# JTAG_Connector.net
KiCad netlist of a schematic drawn in Altium Designer
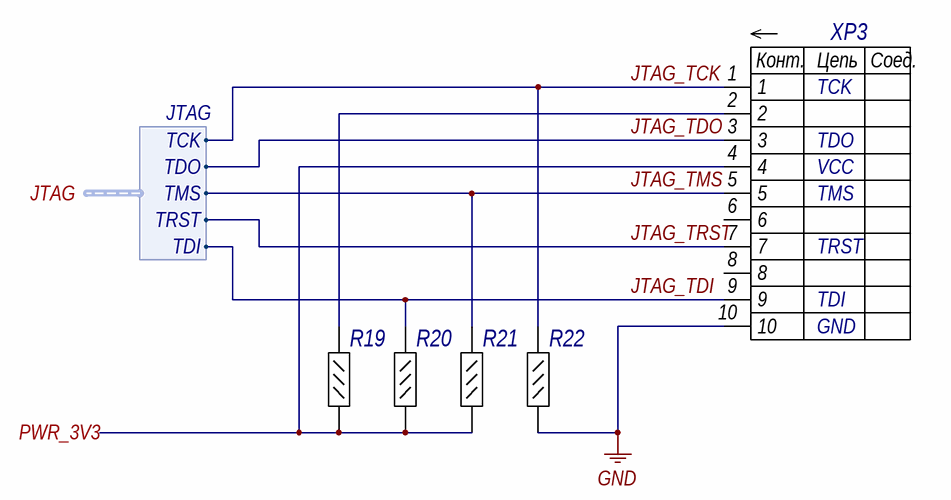
[diagram p0: JTAG Connector.SchDoc]

(export (version "E")
  (design (tool "Eeschema 10.0.6"))
  (components
    (comp (ref "R19")
      (value "ERJ-2RKF1001X")
      (footprint "RESC1005X40X25LL05T05")
      (description "Chip Resistor, 1 KOhm, +/- 1%, 100 mW, -55 to 155 degC, 0402 (1005 Metric), RoHS, Tape and Reel")
      (fields (field (name "TOLERANCE") "1%") (field (name "MANUFACTURER") "Basic Passives"))
      (libsource (lib "") (part "RES-0.05_1"))
    )
    (comp (ref "R20")
      (value "ERJ-2RKF1001X")
      (footprint "RESC1005X40X25LL05T05")
      (description "Chip Resistor, 1 KOhm, +/- 1%, 100 mW, -55 to 155 degC, 0402 (1005 Metric), RoHS, Tape and Reel")
      (fields (field (name "TOLERANCE") "1%") (field (name "MANUFACTURER") "Basic Passives"))
      (libsource (lib "MiniPC DB") (part "RES-0.05"))
    )
    (comp (ref "R21")
      (value "ERJ-2RKF1001X")
      (footprint "RESC1005X40X25LL05T05")
      (description "Chip Resistor, 1 KOhm, +/- 1%, 100 mW, -55 to 155 degC, 0402 (1005 Metric), RoHS, Tape and Reel")
      (fields (field (name "TOLERANCE") "1%") (field (name "MANUFACTURER") "Basic Passives"))
      (libsource (lib "MiniPC DB") (part "RES-0.05"))
    )
    (comp (ref "R22")
      (value "ERJ-2RKF1001X")
      (footprint "RESC1005X40X25LL05T05")
      (description "Chip Resistor, 1 KOhm, +/- 1%, 100 mW, -55 to 155 degC, 0402 (1005 Metric), RoHS, Tape and Reel")
      (fields (field (name "TOLERANCE") "1%") (field (name "MANUFACTURER") "Basic Passives"))
      (libsource (lib "MiniPC DB") (part "RES-0.05"))
    )
    (comp (ref "XP3")
      (value "TSM-105-01-T-DV-TR")
      (footprint "SMTC-TSM-105-01-T-DV_V")
      (description "Male Header, Pitch 2.54 mm, 2 x 5 Position, Height 9.65 mm, -55 to 105 degC, RoHS, Tape and Reel")
      (libsource (lib "MiniPC DB") (part "VILKA_10K"))
    )
  )
  (nets
    (net (code "2") (name "/JTAG_TCK") (class "Default")
      (node (ref "R22") (pin "2") (pinfunction "2_2") (pintype "passive"))
      (node (ref "XP3") (pin "1") (pinfunction "1_1") (pintype "passive"))
    )
    (net (code "3") (name "/JTAG_TDI") (class "Default")
      (node (ref "R20") (pin "2") (pinfunction "2_2") (pintype "passive"))
      (node (ref "XP3") (pin "9") (pinfunction "9_9") (pintype "passive"))
    )
    (net (code "4") (name "/JTAG_TDO") (class "Default")
      (node (ref "XP3") (pin "3") (pinfunction "3_3") (pintype "passive"))
    )
    (net (code "5") (name "/JTAG_TMS") (class "Default")
      (node (ref "R21") (pin "2") (pinfunction "2_2") (pintype "passive"))
      (node (ref "XP3") (pin "5") (pinfunction "5_5") (pintype "passive"))
    )
    (net (code "6") (name "/JTAG_TRST") (class "Default")
      (node (ref "XP3") (pin "7") (pinfunction "7_7") (pintype "passive"))
    )
    (net (code "7") (name "/PWR_3V3") (class "Default")
      (node (ref "R19") (pin "2") (pinfunction "2_2") (pintype "passive"))
      (node (ref "R20") (pin "1") (pinfunction "1_1") (pintype "passive"))
      (node (ref "R21") (pin "1") (pinfunction "1_1") (pintype "passive"))
      (node (ref "XP3") (pin "4") (pinfunction "4_4") (pintype "passive"))
    )
    (net (code "9") (name "GND") (class "Default")
      (node (ref "R22") (pin "1") (pinfunction "1_1") (pintype "passive"))
      (node (ref "XP3") (pin "10") (pinfunction "10_10") (pintype "passive"))
    )
    (net (code "10") (name "Net-(R19-Pad1)") (class "Default")
      (node (ref "R19") (pin "1") (pinfunction "1_1") (pintype "passive"))
      (node (ref "XP3") (pin "2") (pinfunction "2_2") (pintype "passive"))
    )
    (net (code "11") (name "unconnected-(XP3-Pad6)") (class "Default")
      (node (ref "XP3") (pin "6") (pinfunction "6_6") (pintype "passive"))
    )
    (net (code "12") (name "unconnected-(XP3-Pad8)") (class "Default")
      (node (ref "XP3") (pin "8") (pinfunction "8_8") (pintype "passive"))
    )
  )
)
